# RelayBoard.net
KiCad netlist of a schematic drawn in Altium Designer
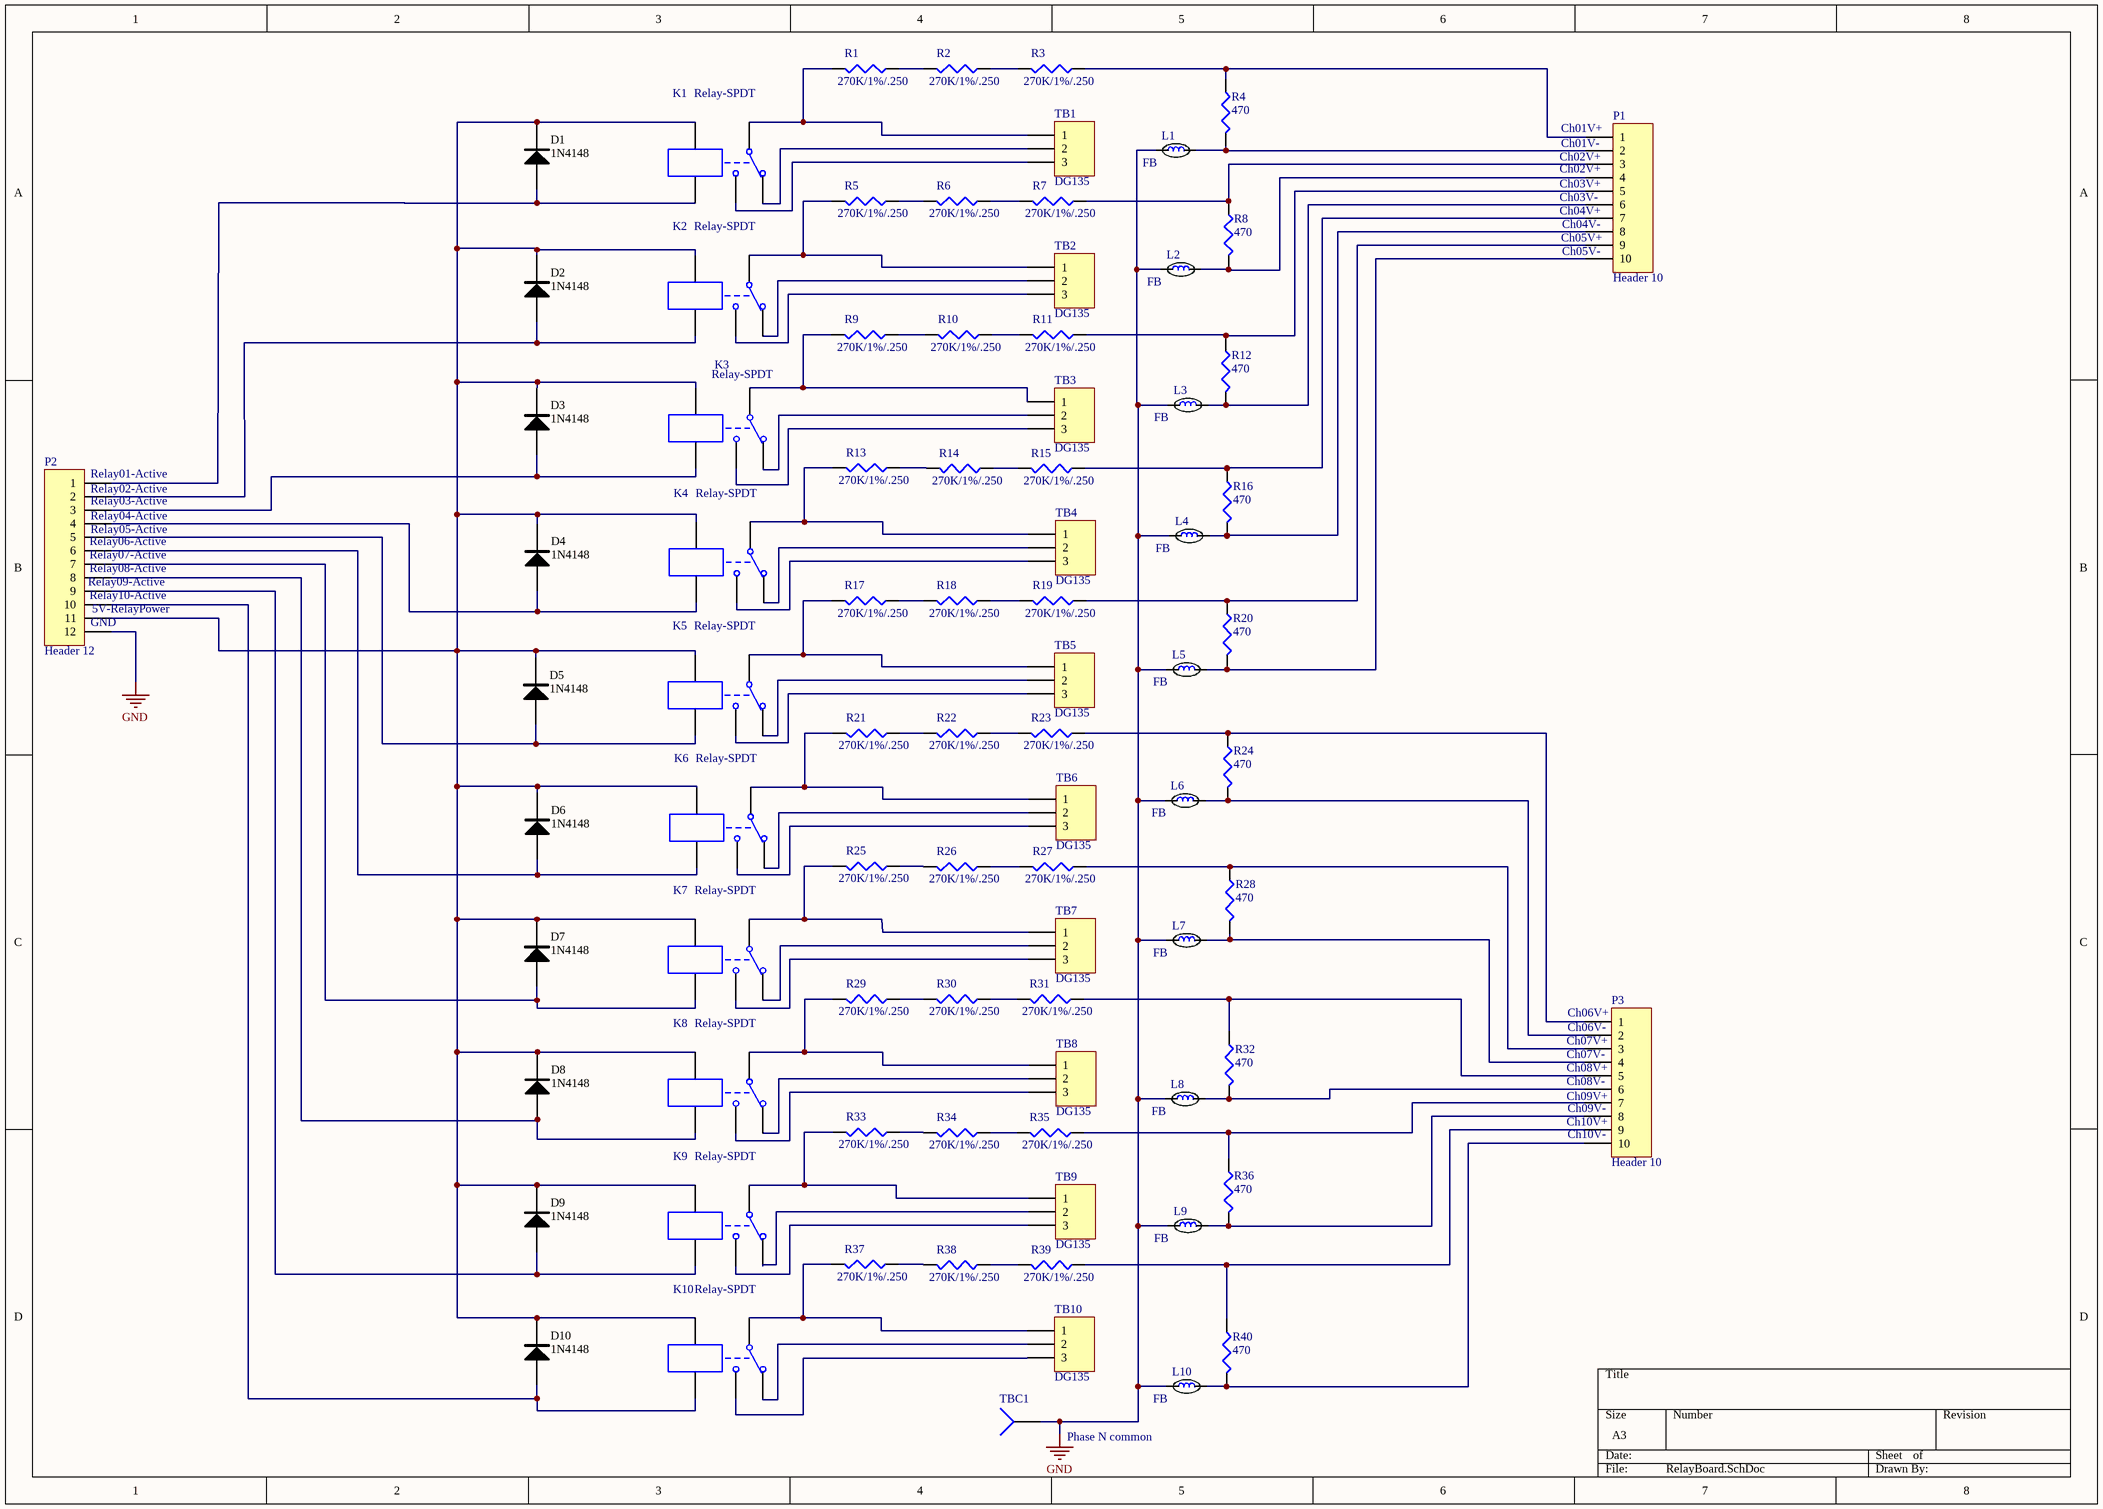
[diagram p0: RelayBoard.SchDoc]

(export (version "E")
  (design (tool "Eeschema 10.0.6"))
  (components
    (comp (ref "D1")
      (value "1N4148")
      (footprint "SOD523")
      (description "1N4001")
      (libsource (lib "vh_altium_library") (part "1N4001"))
    )
    (comp (ref "D2")
      (value "1N4148")
      (footprint "SOD523")
      (description "1N4001")
      (libsource (lib "vh_altium_library") (part "1N4001"))
    )
    (comp (ref "D3")
      (value "1N4148")
      (footprint "SOD523")
      (description "1N4001")
      (libsource (lib "vh_altium_library") (part "1N4001"))
    )
    (comp (ref "D4")
      (value "1N4148")
      (footprint "SOD523")
      (description "1N4001")
      (libsource (lib "vh_altium_library") (part "1N4001"))
    )
    (comp (ref "D5")
      (value "1N4148")
      (footprint "SOD523")
      (description "1N4001")
      (libsource (lib "vh_altium_library") (part "1N4001"))
    )
    (comp (ref "D6")
      (value "1N4148")
      (footprint "SOD523")
      (description "1N4001")
      (libsource (lib "vh_altium_library") (part "1N4001"))
    )
    (comp (ref "D7")
      (value "1N4148")
      (footprint "SOD523")
      (description "1N4001")
      (libsource (lib "vh_altium_library") (part "1N4001"))
    )
    (comp (ref "D8")
      (value "1N4148")
      (footprint "SOD523")
      (description "1N4001")
      (libsource (lib "vh_altium_library") (part "1N4001"))
    )
    (comp (ref "D9")
      (value "1N4148")
      (footprint "SOD523")
      (description "1N4001")
      (libsource (lib "vh_altium_library") (part "1N4001"))
    )
    (comp (ref "D10")
      (value "1N4148")
      (footprint "SOD523")
      (description "1N4001")
      (libsource (lib "vh_altium_library") (part "1N4001"))
    )
    (comp (ref "K1")
      (value "Relay-SPDT")
      (footprint "MODULE5B")
      (description "Single-Pole Dual-Throw Relay")
      (fields (field (name "PUBLISHER") "Altium Limited"))
      (libsource (lib "Miscellaneous Devices") (part "Relay-SPDT"))
    )
    (comp (ref "K2")
      (value "Relay-SPDT")
      (footprint "MODULE5B")
      (description "Single-Pole Dual-Throw Relay")
      (fields (field (name "PUBLISHER") "Altium Limited"))
      (libsource (lib "Miscellaneous Devices") (part "Relay-SPDT"))
    )
    (comp (ref "K3")
      (value "Relay-SPDT")
      (footprint "MODULE5B")
      (description "Single-Pole Dual-Throw Relay")
      (fields (field (name "PUBLISHER") "Altium Limited"))
      (libsource (lib "Miscellaneous Devices") (part "Relay-SPDT"))
    )
    (comp (ref "K4")
      (value "Relay-SPDT")
      (footprint "MODULE5B")
      (description "Single-Pole Dual-Throw Relay")
      (fields (field (name "PUBLISHER") "Altium Limited"))
      (libsource (lib "Miscellaneous Devices") (part "Relay-SPDT"))
    )
    (comp (ref "K5")
      (value "Relay-SPDT")
      (footprint "MODULE5B")
      (description "Single-Pole Dual-Throw Relay")
      (fields (field (name "PUBLISHER") "Altium Limited"))
      (libsource (lib "Miscellaneous Devices") (part "Relay-SPDT"))
    )
    (comp (ref "K6")
      (value "Relay-SPDT")
      (footprint "MODULE5B")
      (description "Single-Pole Dual-Throw Relay")
      (fields (field (name "PUBLISHER") "Altium Limited"))
      (libsource (lib "Miscellaneous Devices") (part "Relay-SPDT"))
    )
    (comp (ref "K7")
      (value "Relay-SPDT")
      (footprint "MODULE5B")
      (description "Single-Pole Dual-Throw Relay")
      (fields (field (name "PUBLISHER") "Altium Limited"))
      (libsource (lib "Miscellaneous Devices") (part "Relay-SPDT"))
    )
    (comp (ref "K8")
      (value "Relay-SPDT")
      (footprint "MODULE5B")
      (description "Single-Pole Dual-Throw Relay")
      (fields (field (name "PUBLISHER") "Altium Limited"))
      (libsource (lib "Miscellaneous Devices") (part "Relay-SPDT"))
    )
    (comp (ref "K9")
      (value "Relay-SPDT")
      (footprint "MODULE5B")
      (description "Single-Pole Dual-Throw Relay")
      (fields (field (name "PUBLISHER") "Altium Limited"))
      (libsource (lib "Miscellaneous Devices") (part "Relay-SPDT"))
    )
    (comp (ref "K10")
      (value "Relay-SPDT")
      (footprint "MODULE5B")
      (description "Single-Pole Dual-Throw Relay")
      (fields (field (name "PUBLISHER") "Altium Limited"))
      (libsource (lib "Miscellaneous Devices") (part "Relay-SPDT"))
    )
    (comp (ref "L1") (value "FB") (footprint "0603C-TBD") (libsource (lib "SMLib") (part "FerrBeads/ILBB")))
    (comp (ref "L2") (value "FB") (footprint "0603C-TBD") (libsource (lib "SMLib") (part "FerrBeads/ILBB")))
    (comp (ref "L3") (value "FB") (footprint "0603C-TBD") (libsource (lib "SMLib") (part "FerrBeads/ILBB")))
    (comp (ref "L4") (value "FB") (footprint "0603C-TBD") (libsource (lib "SMLib") (part "FerrBeads/ILBB")))
    (comp (ref "L5") (value "FB") (footprint "0603C-TBD") (libsource (lib "SMLib") (part "FerrBeads/ILBB")))
    (comp (ref "L6") (value "FB") (footprint "0603C-TBD") (libsource (lib "SMLib") (part "FerrBeads/ILBB")))
    (comp (ref "L7") (value "FB") (footprint "0603C-TBD") (libsource (lib "SMLib") (part "FerrBeads/ILBB")))
    (comp (ref "L8") (value "FB") (footprint "0603C-TBD") (libsource (lib "SMLib") (part "FerrBeads/ILBB")))
    (comp (ref "L9") (value "FB") (footprint "0603C-TBD") (libsource (lib "SMLib") (part "FerrBeads/ILBB")))
    (comp (ref "L10") (value "FB") (footprint "0603C-TBD") (libsource (lib "SMLib") (part "FerrBeads/ILBB")))
    (comp (ref "P1")
      (value "Header 10")
      (footprint "HDR1X10")
      (description "Header, 10-Pin")
      (fields (field (name "PUBLISHER") "Altium Limited"))
      (libsource (lib "Miscellaneous Connectors") (part "Header 10"))
    )
    (comp (ref "P2")
      (value "Header 12")
      (footprint "HDR1X12")
      (description "Header, 12-Pin")
      (fields (field (name "PUBLISHER") "Altium Limited"))
      (libsource (lib "Miscellaneous Connectors") (part "Header 12"))
    )
    (comp (ref "P3")
      (value "Header 10")
      (footprint "HDR1X10")
      (description "Header, 10-Pin")
      (fields (field (name "PUBLISHER") "Altium Limited"))
      (libsource (lib "Miscellaneous Connectors") (part "Header 10"))
    )
    (comp (ref "R1")
      (value "270K/1%/.250")
      (footprint "1210C-GENERIC")
      (description "Resistor")
      (fields (field (name "PUBLISHER") "Altium Limited"))
      (libsource (lib "Miscellaneous Devices") (part "Res3"))
    )
    (comp (ref "R2")
      (value "270K/1%/.250")
      (footprint "1210C-GENERIC")
      (description "Resistor")
      (fields (field (name "PUBLISHER") "Altium Limited"))
      (libsource (lib "Miscellaneous Devices") (part "Res3"))
    )
    (comp (ref "R3")
      (value "270K/1%/.250")
      (footprint "1210C-GENERIC")
      (description "Resistor")
      (fields (field (name "PUBLISHER") "Altium Limited"))
      (libsource (lib "Miscellaneous Devices") (part "Res3"))
    )
    (comp (ref "R4")
      (value "470")
      (footprint "1206C-GENERIC")
      (description "Resistor")
      (fields (field (name "PUBLISHER") "Altium Limited"))
      (libsource (lib "Miscellaneous Devices") (part "Res3"))
    )
    (comp (ref "R5")
      (value "270K/1%/.250")
      (footprint "1210C-GENERIC")
      (description "Resistor")
      (fields (field (name "PUBLISHER") "Altium Limited"))
      (libsource (lib "Miscellaneous Devices") (part "Res3"))
    )
    (comp (ref "R6")
      (value "270K/1%/.250")
      (footprint "1210C-GENERIC")
      (description "Resistor")
      (fields (field (name "PUBLISHER") "Altium Limited"))
      (libsource (lib "Miscellaneous Devices") (part "Res3"))
    )
    (comp (ref "R7")
      (value "270K/1%/.250")
      (footprint "1210C-GENERIC")
      (description "Resistor")
      (fields (field (name "PUBLISHER") "Altium Limited"))
      (libsource (lib "Miscellaneous Devices") (part "Res3"))
    )
    (comp (ref "R8")
      (value "470")
      (footprint "1206C-GENERIC")
      (description "Resistor")
      (fields (field (name "PUBLISHER") "Altium Limited"))
      (libsource (lib "Miscellaneous Devices") (part "Res3"))
    )
    (comp (ref "R9")
      (value "270K/1%/.250")
      (footprint "1210C-GENERIC")
      (description "Resistor")
      (fields (field (name "PUBLISHER") "Altium Limited"))
      (libsource (lib "Miscellaneous Devices") (part "Res3"))
    )
    (comp (ref "R10")
      (value "270K/1%/.250")
      (footprint "1210C-GENERIC")
      (description "Resistor")
      (fields (field (name "PUBLISHER") "Altium Limited"))
      (libsource (lib "Miscellaneous Devices") (part "Res3"))
    )
    (comp (ref "R11")
      (value "270K/1%/.250")
      (footprint "1210C-GENERIC")
      (description "Resistor")
      (fields (field (name "PUBLISHER") "Altium Limited"))
      (libsource (lib "Miscellaneous Devices") (part "Res3"))
    )
    (comp (ref "R12")
      (value "470")
      (footprint "1206C-GENERIC")
      (description "Resistor")
      (fields (field (name "PUBLISHER") "Altium Limited"))
      (libsource (lib "Miscellaneous Devices") (part "Res3"))
    )
    (comp (ref "R13")
      (value "270K/1%/.250")
      (footprint "1210C-GENERIC")
      (description "Resistor")
      (fields (field (name "PUBLISHER") "Altium Limited"))
      (libsource (lib "Miscellaneous Devices") (part "Res3"))
    )
    (comp (ref "R14")
      (value "270K/1%/.250")
      (footprint "1210C-GENERIC")
      (description "Resistor")
      (fields (field (name "PUBLISHER") "Altium Limited"))
      (libsource (lib "Miscellaneous Devices") (part "Res3"))
    )
    (comp (ref "R15")
      (value "270K/1%/.250")
      (footprint "1210C-GENERIC")
      (description "Resistor")
      (fields (field (name "PUBLISHER") "Altium Limited"))
      (libsource (lib "Miscellaneous Devices") (part "Res3"))
    )
    (comp (ref "R16")
      (value "470")
      (footprint "1206C-GENERIC")
      (description "Resistor")
      (fields (field (name "PUBLISHER") "Altium Limited"))
      (libsource (lib "Miscellaneous Devices") (part "Res3"))
    )
    (comp (ref "R17")
      (value "270K/1%/.250")
      (footprint "1210C-GENERIC")
      (description "Resistor")
      (fields (field (name "PUBLISHER") "Altium Limited"))
      (libsource (lib "Miscellaneous Devices") (part "Res3"))
    )
    (comp (ref "R18")
      (value "270K/1%/.250")
      (footprint "1210C-GENERIC")
      (description "Resistor")
      (fields (field (name "PUBLISHER") "Altium Limited"))
      (libsource (lib "Miscellaneous Devices") (part "Res3"))
    )
    (comp (ref "R19")
      (value "270K/1%/.250")
      (footprint "1210C-GENERIC")
      (description "Resistor")
      (fields (field (name "PUBLISHER") "Altium Limited"))
      (libsource (lib "Miscellaneous Devices") (part "Res3"))
    )
    (comp (ref "R20")
      (value "470")
      (footprint "1206C-GENERIC")
      (description "Resistor")
      (fields (field (name "PUBLISHER") "Altium Limited"))
      (libsource (lib "Miscellaneous Devices") (part "Res3"))
    )
    (comp (ref "R21")
      (value "270K/1%/.250")
      (footprint "1210C-GENERIC")
      (description "Resistor")
      (fields (field (name "PUBLISHER") "Altium Limited"))
      (libsource (lib "Miscellaneous Devices") (part "Res3"))
    )
    (comp (ref "R22")
      (value "270K/1%/.250")
      (footprint "1210C-GENERIC")
      (description "Resistor")
      (fields (field (name "PUBLISHER") "Altium Limited"))
      (libsource (lib "Miscellaneous Devices") (part "Res3"))
    )
    (comp (ref "R23")
      (value "270K/1%/.250")
      (footprint "1210C-GENERIC")
      (description "Resistor")
      (fields (field (name "PUBLISHER") "Altium Limited"))
      (libsource (lib "Miscellaneous Devices") (part "Res3"))
    )
    (comp (ref "R24")
      (value "470")
      (footprint "1206C-GENERIC")
      (description "Resistor")
      (fields (field (name "PUBLISHER") "Altium Limited"))
      (libsource (lib "Miscellaneous Devices") (part "Res3"))
    )
    (comp (ref "R25")
      (value "270K/1%/.250")
      (footprint "1210C-GENERIC")
      (description "Resistor")
      (fields (field (name "PUBLISHER") "Altium Limited"))
      (libsource (lib "Miscellaneous Devices") (part "Res3"))
    )
    (comp (ref "R26")
      (value "270K/1%/.250")
      (footprint "1210C-GENERIC")
      (description "Resistor")
      (fields (field (name "PUBLISHER") "Altium Limited"))
      (libsource (lib "Miscellaneous Devices") (part "Res3"))
    )
    (comp (ref "R27")
      (value "270K/1%/.250")
      (footprint "1210C-GENERIC")
      (description "Resistor")
      (fields (field (name "PUBLISHER") "Altium Limited"))
      (libsource (lib "Miscellaneous Devices") (part "Res3"))
    )
    (comp (ref "R28")
      (value "470")
      (footprint "1206C-GENERIC")
      (description "Resistor")
      (fields (field (name "PUBLISHER") "Altium Limited"))
      (libsource (lib "Miscellaneous Devices") (part "Res3"))
    )
    (comp (ref "R29")
      (value "270K/1%/.250")
      (footprint "1210C-GENERIC")
      (description "Resistor")
      (fields (field (name "PUBLISHER") "Altium Limited"))
      (libsource (lib "Miscellaneous Devices") (part "Res3"))
    )
    (comp (ref "R30")
      (value "270K/1%/.250")
      (footprint "1210C-GENERIC")
      (description "Resistor")
      (fields (field (name "PUBLISHER") "Altium Limited"))
      (libsource (lib "Miscellaneous Devices") (part "Res3"))
    )
    (comp (ref "R31")
      (value "270K/1%/.250")
      (footprint "1210C-GENERIC")
      (description "Resistor")
      (fields (field (name "PUBLISHER") "Altium Limited"))
      (libsource (lib "Miscellaneous Devices") (part "Res3"))
    )
    (comp (ref "R32")
      (value "470")
      (footprint "1206C-GENERIC")
      (description "Resistor")
      (fields (field (name "PUBLISHER") "Altium Limited"))
      (libsource (lib "Miscellaneous Devices") (part "Res3"))
    )
    (comp (ref "R33")
      (value "270K/1%/.250")
      (footprint "1210C-GENERIC")
      (description "Resistor")
      (fields (field (name "PUBLISHER") "Altium Limited"))
      (libsource (lib "Miscellaneous Devices") (part "Res3"))
    )
    (comp (ref "R34")
      (value "270K/1%/.250")
      (footprint "1210C-GENERIC")
      (description "Resistor")
      (fields (field (name "PUBLISHER") "Altium Limited"))
      (libsource (lib "Miscellaneous Devices") (part "Res3"))
    )
    (comp (ref "R35")
      (value "270K/1%/.250")
      (footprint "1210C-GENERIC")
      (description "Resistor")
      (fields (field (name "PUBLISHER") "Altium Limited"))
      (libsource (lib "Miscellaneous Devices") (part "Res3"))
    )
    (comp (ref "R36")
      (value "470")
      (footprint "1206C-GENERIC")
      (description "Resistor")
      (fields (field (name "PUBLISHER") "Altium Limited"))
      (libsource (lib "Miscellaneous Devices") (part "Res3"))
    )
    (comp (ref "R37")
      (value "270K/1%/.250")
      (footprint "1210C-GENERIC")
      (description "Resistor")
      (fields (field (name "PUBLISHER") "Altium Limited"))
      (libsource (lib "Miscellaneous Devices") (part "Res3"))
    )
    (comp (ref "R38")
      (value "270K/1%/.250")
      (footprint "1210C-GENERIC")
      (description "Resistor")
      (fields (field (name "PUBLISHER") "Altium Limited"))
      (libsource (lib "Miscellaneous Devices") (part "Res3"))
    )
    (comp (ref "R39")
      (value "270K/1%/.250")
      (footprint "1210C-GENERIC")
      (description "Resistor")
      (fields (field (name "PUBLISHER") "Altium Limited"))
      (libsource (lib "Miscellaneous Devices") (part "Res3"))
    )
    (comp (ref "R40")
      (value "470")
      (footprint "1206C-GENERIC")
      (description "Resistor")
      (fields (field (name "PUBLISHER") "Altium Limited"))
      (libsource (lib "Miscellaneous Devices") (part "Res3"))
    )
    (comp (ref "TB1")
      (value "DG135")
      (footprint "DG135-1")
      (description "Header, 3-Pin")
      (fields (field (name "PUBLISHER") "Altium Limited"))
      (libsource (lib "Miscellaneous Connectors") (part "Header 3"))
    )
    (comp (ref "TB2")
      (value "DG135")
      (footprint "DG135-1")
      (description "Header, 3-Pin")
      (fields (field (name "PUBLISHER") "Altium Limited"))
      (libsource (lib "Miscellaneous Connectors") (part "Header 3"))
    )
    (comp (ref "TB3")
      (value "DG135")
      (footprint "DG135-1")
      (description "Header, 3-Pin")
      (fields (field (name "PUBLISHER") "Altium Limited"))
      (libsource (lib "Miscellaneous Connectors") (part "Header 3"))
    )
    (comp (ref "TB4")
      (value "DG135")
      (footprint "DG135-1")
      (description "Header, 3-Pin")
      (fields (field (name "PUBLISHER") "Altium Limited"))
      (libsource (lib "Miscellaneous Connectors") (part "Header 3"))
    )
    (comp (ref "TB5")
      (value "DG135")
      (footprint "DG135-1")
      (description "Header, 3-Pin")
      (fields (field (name "PUBLISHER") "Altium Limited"))
      (libsource (lib "Miscellaneous Connectors") (part "Header 3"))
    )
    (comp (ref "TB6")
      (value "DG135")
      (footprint "DG135-1")
      (description "Header, 3-Pin")
      (fields (field (name "PUBLISHER") "Altium Limited"))
      (libsource (lib "Miscellaneous Connectors") (part "Header 3"))
    )
    (comp (ref "TB7")
      (value "DG135")
      (footprint "DG135-1")
      (description "Header, 3-Pin")
      (fields (field (name "PUBLISHER") "Altium Limited"))
      (libsource (lib "Miscellaneous Connectors") (part "Header 3"))
    )
    (comp (ref "TB8")
      (value "DG135")
      (footprint "DG135-1")
      (description "Header, 3-Pin")
      (fields (field (name "PUBLISHER") "Altium Limited"))
      (libsource (lib "Miscellaneous Connectors") (part "Header 3"))
    )
    (comp (ref "TB9")
      (value "DG135")
      (footprint "DG135-1")
      (description "Header, 3-Pin")
      (fields (field (name "PUBLISHER") "Altium Limited"))
      (libsource (lib "Miscellaneous Connectors") (part "Header 3"))
    )
    (comp (ref "TB10")
      (value "DG135")
      (footprint "DG135-1")
      (description "Header, 3-Pin")
      (fields (field (name "PUBLISHER") "Altium Limited"))
      (libsource (lib "Miscellaneous Connectors") (part "Header 3"))
    )
    (comp (ref "TBC1")
      (value "TBcommon")
      (footprint "PIN1")
      (description "Socket")
      (fields (field (name "PUBLISHER") "Altium Limited"))
      (libsource (lib "Miscellaneous Connectors") (part "Socket"))
    )
  )
  (nets
    (net (code "1") (name "GND") (class "Default")
      (node (ref "L1") (pin "1") (pinfunction "1_1") (pintype "passive"))
      (node (ref "L10") (pin "1") (pinfunction "1_1") (pintype "passive"))
      (node (ref "L2") (pin "1") (pinfunction "1_1") (pintype "passive"))
      (node (ref "L3") (pin "1") (pinfunction "1_1") (pintype "passive"))
      (node (ref "L4") (pin "1") (pinfunction "1_1") (pintype "passive"))
      (node (ref "L5") (pin "1") (pinfunction "1_1") (pintype "passive"))
      (node (ref "L6") (pin "1") (pinfunction "1_1") (pintype "passive"))
      (node (ref "L7") (pin "1") (pinfunction "1_1") (pintype "passive"))
      (node (ref "L8") (pin "1") (pinfunction "1_1") (pintype "passive"))
      (node (ref "L9") (pin "1") (pinfunction "1_1") (pintype "passive"))
      (node (ref "P2") (pin "12") (pinfunction "12_12") (pintype "passive"))
      (node (ref "TBC1") (pin "1") (pinfunction "1_1") (pintype "passive"))
    )
    (net (code "2") (name "Net-(D1-PadA)") (class "Default")
      (node (ref "D1") (pin "A") (pinfunction "A_A") (pintype "passive"))
      (node (ref "K1") (pin "2") (pinfunction "2_2") (pintype "passive"))
      (node (ref "P2") (pin "1") (pinfunction "1_1") (pintype "passive"))
    )
    (net (code "3") (name "Net-(D1-PadK)") (class "Default")
      (node (ref "D1") (pin "K") (pinfunction "K_K") (pintype "passive"))
      (node (ref "D10") (pin "K") (pinfunction "K_K") (pintype "passive"))
      (node (ref "D2") (pin "K") (pinfunction "K_K") (pintype "passive"))
      (node (ref "D3") (pin "K") (pinfunction "K_K") (pintype "passive"))
      (node (ref "D4") (pin "K") (pinfunction "K_K") (pintype "passive"))
      (node (ref "D5") (pin "K") (pinfunction "K_K") (pintype "passive"))
      (node (ref "D6") (pin "K") (pinfunction "K_K") (pintype "passive"))
      (node (ref "D7") (pin "K") (pinfunction "K_K") (pintype "passive"))
      (node (ref "D8") (pin "K") (pinfunction "K_K") (pintype "passive"))
      (node (ref "D9") (pin "K") (pinfunction "K_K") (pintype "passive"))
      (node (ref "K1") (pin "1") (pinfunction "1_1") (pintype "passive"))
      (node (ref "K10") (pin "1") (pinfunction "1_1") (pintype "passive"))
      (node (ref "K2") (pin "1") (pinfunction "1_1") (pintype "passive"))
      (node (ref "K3") (pin "1") (pinfunction "1_1") (pintype "passive"))
      (node (ref "K4") (pin "1") (pinfunction "1_1") (pintype "passive"))
      (node (ref "K5") (pin "1") (pinfunction "1_1") (pintype "passive"))
      (node (ref "K6") (pin "1") (pinfunction "1_1") (pintype "passive"))
      (node (ref "K7") (pin "1") (pinfunction "1_1") (pintype "passive"))
      (node (ref "K8") (pin "1") (pinfunction "1_1") (pintype "passive"))
      (node (ref "K9") (pin "1") (pinfunction "1_1") (pintype "passive"))
      (node (ref "P2") (pin "11") (pinfunction "11_11") (pintype "passive"))
    )
    (net (code "4") (name "Net-(D2-PadA)") (class "Default")
      (node (ref "D2") (pin "A") (pinfunction "A_A") (pintype "passive"))
      (node (ref "K2") (pin "2") (pinfunction "2_2") (pintype "passive"))
      (node (ref "P2") (pin "2") (pinfunction "2_2") (pintype "passive"))
    )
    (net (code "5") (name "Net-(D3-PadA)") (class "Default")
      (node (ref "D3") (pin "A") (pinfunction "A_A") (pintype "passive"))
      (node (ref "K3") (pin "2") (pinfunction "2_2") (pintype "passive"))
      (node (ref "P2") (pin "3") (pinfunction "3_3") (pintype "passive"))
    )
    (net (code "6") (name "Net-(D4-PadA)") (class "Default")
      (node (ref "D4") (pin "A") (pinfunction "A_A") (pintype "passive"))
      (node (ref "K4") (pin "2") (pinfunction "2_2") (pintype "passive"))
      (node (ref "P2") (pin "4") (pinfunction "4_4") (pintype "passive"))
    )
    (net (code "7") (name "Net-(D5-PadA)") (class "Default")
      (node (ref "D5") (pin "A") (pinfunction "A_A") (pintype "passive"))
      (node (ref "K5") (pin "2") (pinfunction "2_2") (pintype "passive"))
      (node (ref "P2") (pin "5") (pinfunction "5_5") (pintype "passive"))
    )
    (net (code "8") (name "Net-(D6-PadA)") (class "Default")
      (node (ref "D6") (pin "A") (pinfunction "A_A") (pintype "passive"))
      (node (ref "K6") (pin "2") (pinfunction "2_2") (pintype "passive"))
      (node (ref "P2") (pin "6") (pinfunction "6_6") (pintype "passive"))
    )
    (net (code "9") (name "Net-(D7-PadA)") (class "Default")
      (node (ref "D7") (pin "A") (pinfunction "A_A") (pintype "passive"))
      (node (ref "K7") (pin "2") (pinfunction "2_2") (pintype "passive"))
      (node (ref "P2") (pin "7") (pinfunction "7_7") (pintype "passive"))
    )
    (net (code "10") (name "Net-(D8-PadA)") (class "Default")
      (node (ref "D8") (pin "A") (pinfunction "A_A") (pintype "passive"))
      (node (ref "K8") (pin "2") (pinfunction "2_2") (pintype "passive"))
      (node (ref "P2") (pin "8") (pinfunction "8_8") (pintype "passive"))
    )
    (net (code "11") (name "Net-(D9-PadA)") (class "Default")
      (node (ref "D9") (pin "A") (pinfunction "A_A") (pintype "passive"))
      (node (ref "K9") (pin "2") (pinfunction "2_2") (pintype "passive"))
      (node (ref "P2") (pin "9") (pinfunction "9_9") (pintype "passive"))
    )
    (net (code "12") (name "Net-(D10-PadA)") (class "Default")
      (node (ref "D10") (pin "A") (pinfunction "A_A") (pintype "passive"))
      (node (ref "K10") (pin "2") (pinfunction "2_2") (pintype "passive"))
      (node (ref "P2") (pin "10") (pinfunction "10_10") (pintype "passive"))
    )
    (net (code "13") (name "Net-(K1-Pad3)") (class "Default")
      (node (ref "K1") (pin "3") (pinfunction "3_3") (pintype "passive"))
      (node (ref "TB1") (pin "3") (pinfunction "3_3") (pintype "passive"))
    )
    (net (code "14") (name "Net-(K1-Pad4)") (class "Default")
      (node (ref "K1") (pin "4") (pinfunction "4_4") (pintype "passive"))
      (node (ref "R1") (pin "2") (pinfunction "2_2") (pintype "passive"))
      (node (ref "TB1") (pin "1") (pinfunction "1_1") (pintype "passive"))
    )
    (net (code "15") (name "Net-(K1-Pad5)") (class "Default")
      (node (ref "K1") (pin "5") (pinfunction "5_5") (pintype "passive"))
      (node (ref "TB1") (pin "2") (pinfunction "2_2") (pintype "passive"))
    )
    (net (code "16") (name "Net-(K2-Pad3)") (class "Default")
      (node (ref "K2") (pin "3") (pinfunction "3_3") (pintype "passive"))
      (node (ref "TB2") (pin "3") (pinfunction "3_3") (pintype "passive"))
    )
    (net (code "17") (name "Net-(K2-Pad4)") (class "Default")
      (node (ref "K2") (pin "4") (pinfunction "4_4") (pintype "passive"))
      (node (ref "R5") (pin "2") (pinfunction "2_2") (pintype "passive"))
      (node (ref "TB2") (pin "1") (pinfunction "1_1") (pintype "passive"))
    )
    (net (code "18") (name "Net-(K2-Pad5)") (class "Default")
      (node (ref "K2") (pin "5") (pinfunction "5_5") (pintype "passive"))
      (node (ref "TB2") (pin "2") (pinfunction "2_2") (pintype "passive"))
    )
    (net (code "19") (name "Net-(K3-Pad3)") (class "Default")
      (node (ref "K3") (pin "3") (pinfunction "3_3") (pintype "passive"))
      (node (ref "TB3") (pin "3") (pinfunction "3_3") (pintype "passive"))
    )
    (net (code "20") (name "Net-(K3-Pad4)") (class "Default")
      (node (ref "K3") (pin "4") (pinfunction "4_4") (pintype "passive"))
      (node (ref "R9") (pin "2") (pinfunction "2_2") (pintype "passive"))
      (node (ref "TB3") (pin "1") (pinfunction "1_1") (pintype "passive"))
    )
    (net (code "21") (name "Net-(K3-Pad5)") (class "Default")
      (node (ref "K3") (pin "5") (pinfunction "5_5") (pintype "passive"))
      (node (ref "TB3") (pin "2") (pinfunction "2_2") (pintype "passive"))
    )
    (net (code "22") (name "Net-(K4-Pad3)") (class "Default")
      (node (ref "K4") (pin "3") (pinfunction "3_3") (pintype "passive"))
      (node (ref "TB4") (pin "3") (pinfunction "3_3") (pintype "passive"))
    )
    (net (code "23") (name "Net-(K4-Pad4)") (class "Default")
      (node (ref "K4") (pin "4") (pinfunction "4_4") (pintype "passive"))
      (node (ref "R13") (pin "2") (pinfunction "2_2") (pintype "passive"))
      (node (ref "TB4") (pin "1") (pinfunction "1_1") (pintype "passive"))
    )
    (net (code "24") (name "Net-(K4-Pad5)") (class "Default")
      (node (ref "K4") (pin "5") (pinfunction "5_5") (pintype "passive"))
      (node (ref "TB4") (pin "2") (pinfunction "2_2") (pintype "passive"))
    )
    (net (code "25") (name "Net-(K5-Pad3)") (class "Default")
      (node (ref "K5") (pin "3") (pinfunction "3_3") (pintype "passive"))
      (node (ref "TB5") (pin "3") (pinfunction "3_3") (pintype "passive"))
    )
    (net (code "26") (name "Net-(K5-Pad4)") (class "Default")
      (node (ref "K5") (pin "4") (pinfunction "4_4") (pintype "passive"))
      (node (ref "R17") (pin "2") (pinfunction "2_2") (pintype "passive"))
      (node (ref "TB5") (pin "1") (pinfunction "1_1") (pintype "passive"))
    )
    (net (code "27") (name "Net-(K5-Pad5)") (class "Default")
      (node (ref "K5") (pin "5") (pinfunction "5_5") (pintype "passive"))
      (node (ref "TB5") (pin "2") (pinfunction "2_2") (pintype "passive"))
    )
    (net (code "28") (name "Net-(K6-Pad3)") (class "Default")
      (node (ref "K6") (pin "3") (pinfunction "3_3") (pintype "passive"))
      (node (ref "TB6") (pin "3") (pinfunction "3_3") (pintype "passive"))
    )
    (net (code "29") (name "Net-(K6-Pad4)") (class "Default")
      (node (ref "K6") (pin "4") (pinfunction "4_4") (pintype "passive"))
      (node (ref "R21") (pin "2") (pinfunction "2_2") (pintype "passive"))
      (node (ref "TB6") (pin "1") (pinfunction "1_1") (pintype "passive"))
    )
    (net (code "30") (name "Net-(K6-Pad5)") (class "Default")
      (node (ref "K6") (pin "5") (pinfunction "5_5") (pintype "passive"))
      (node (ref "TB6") (pin "2") (pinfunction "2_2") (pintype "passive"))
    )
    (net (code "31") (name "Net-(K7-Pad3)") (class "Default")
      (node (ref "K7") (pin "3") (pinfunction "3_3") (pintype "passive"))
      (node (ref "TB7") (pin "3") (pinfunction "3_3") (pintype "passive"))
    )
    (net (code "32") (name "Net-(K7-Pad4)") (class "Default")
      (node (ref "K7") (pin "4") (pinfunction "4_4") (pintype "passive"))
      (node (ref "R25") (pin "2") (pinfunction "2_2") (pintype "passive"))
      (node (ref "TB7") (pin "1") (pinfunction "1_1") (pintype "passive"))
    )
    (net (code "33") (name "Net-(K7-Pad5)") (class "Default")
      (node (ref "K7") (pin "5") (pinfunction "5_5") (pintype "passive"))
      (node (ref "TB7") (pin "2") (pinfunction "2_2") (pintype "passive"))
    )
    (net (code "34") (name "Net-(K8-Pad3)") (class "Default")
      (node (ref "K8") (pin "3") (pinfunction "3_3") (pintype "passive"))
      (node (ref "TB8") (pin "3") (pinfunction "3_3") (pintype "passive"))
    )
    (net (code "35") (name "Net-(K8-Pad4)") (class "Default")
      (node (ref "K8") (pin "4") (pinfunction "4_4") (pintype "passive"))
      (node (ref "R29") (pin "2") (pinfunction "2_2") (pintype "passive"))
      (node (ref "TB8") (pin "1") (pinfunction "1_1") (pintype "passive"))
    )
    (net (code "36") (name "Net-(K8-Pad5)") (class "Default")
      (node (ref "K8") (pin "5") (pinfunction "5_5") (pintype "passive"))
      (node (ref "TB8") (pin "2") (pinfunction "2_2") (pintype "passive"))
    )
    (net (code "37") (name "Net-(K9-Pad3)") (class "Default")
      (node (ref "K9") (pin "3") (pinfunction "3_3") (pintype "passive"))
      (node (ref "TB9") (pin "3") (pinfunction "3_3") (pintype "passive"))
    )
    (net (code "38") (name "Net-(K9-Pad4)") (class "Default")
      (node (ref "K9") (pin "4") (pinfunction "4_4") (pintype "passive"))
      (node (ref "R33") (pin "2") (pinfunction "2_2") (pintype "passive"))
      (node (ref "TB9") (pin "1") (pinfunction "1_1") (pintype "passive"))
    )
    (net (code "39") (name "Net-(K9-Pad5)") (class "Default")
      (node (ref "K9") (pin "5") (pinfunction "5_5") (pintype "passive"))
      (node (ref "TB9") (pin "2") (pinfunction "2_2") (pintype "passive"))
    )
    (net (code "40") (name "Net-(K10-Pad3)") (class "Default")
      (node (ref "K10") (pin "3") (pinfunction "3_3") (pintype "passive"))
      (node (ref "TB10") (pin "3") (pinfunction "3_3") (pintype "passive"))
    )
    (net (code "41") (name "Net-(K10-Pad4)") (class "Default")
      (node (ref "K10") (pin "4") (pinfunction "4_4") (pintype "passive"))
      (node (ref "R37") (pin "2") (pinfunction "2_2") (pintype "passive"))
      (node (ref "TB10") (pin "1") (pinfunction "1_1") (pintype "passive"))
    )
    (net (code "42") (name "Net-(K10-Pad5)") (class "Default")
      (node (ref "K10") (pin "5") (pinfunction "5_5") (pintype "passive"))
      (node (ref "TB10") (pin "2") (pinfunction "2_2") (pintype "passive"))
    )
    (net (code "43") (name "Net-(L1-Pad2)") (class "Default")
      (node (ref "L1") (pin "2") (pinfunction "2_2") (pintype "passive"))
      (node (ref "P1") (pin "2") (pinfunction "2_2") (pintype "passive"))
      (node (ref "R4") (pin "2") (pinfunction "2_2") (pintype "passive"))
    )
    (net (code "44") (name "Net-(L2-Pad2)") (class "Default")
      (node (ref "L2") (pin "2") (pinfunction "2_2") (pintype "passive"))
      (node (ref "P1") (pin "4") (pinfunction "4_4") (pintype "passive"))
    )
    (net (code "45") (name "Net-(L3-Pad2)") (class "Default")
      (node (ref "L3") (pin "2") (pinfunction "2_2") (pintype "passive"))
      (node (ref "P1") (pin "6") (pinfunction "6_6") (pintype "passive"))
      (node (ref "R12") (pin "2") (pinfunction "2_2") (pintype "passive"))
    )
    (net (code "46") (name "Net-(L4-Pad2)") (class "Default")
      (node (ref "L4") (pin "2") (pinfunction "2_2") (pintype "passive"))
      (node (ref "P1") (pin "8") (pinfunction "8_8") (pintype "passive"))
      (node (ref "R16") (pin "2") (pinfunction "2_2") (pintype "passive"))
    )
    (net (code "47") (name "Net-(L5-Pad2)") (class "Default")
      (node (ref "L5") (pin "2") (pinfunction "2_2") (pintype "passive"))
      (node (ref "P1") (pin "10") (pinfunction "10_10") (pintype "passive"))
    )
    (net (code "48") (name "Net-(L6-Pad2)") (class "Default")
      (node (ref "L6") (pin "2") (pinfunction "2_2") (pintype "passive"))
      (node (ref "P3") (pin "2") (pinfunction "2_2") (pintype "passive"))
      (node (ref "R24") (pin "2") (pinfunction "2_2") (pintype "passive"))
    )
    (net (code "49") (name "Net-(L7-Pad2)") (class "Default")
      (node (ref "L7") (pin "2") (pinfunction "2_2") (pintype "passive"))
      (node (ref "P3") (pin "4") (pinfunction "4_4") (pintype "passive"))
      (node (ref "R28") (pin "2") (pinfunction "2_2") (pintype "passive"))
    )
    (net (code "50") (name "Net-(L8-Pad2)") (class "Default")
      (node (ref "L8") (pin "2") (pinfunction "2_2") (pintype "passive"))
      (node (ref "P3") (pin "6") (pinfunction "6_6") (pintype "passive"))
      (node (ref "R32") (pin "2") (pinfunction "2_2") (pintype "passive"))
    )
    (net (code "51") (name "Net-(L9-Pad2)") (class "Default")
      (node (ref "L9") (pin "2") (pinfunction "2_2") (pintype "passive"))
      (node (ref "P3") (pin "8") (pinfunction "8_8") (pintype "passive"))
      (node (ref "R36") (pin "2") (pinfunction "2_2") (pintype "passive"))
    )
    (net (code "52") (name "Net-(L10-Pad2)") (class "Default")
      (node (ref "L10") (pin "2") (pinfunction "2_2") (pintype "passive"))
      (node (ref "P3") (pin "10") (pinfunction "10_10") (pintype "passive"))
      (node (ref "R40") (pin "2") (pinfunction "2_2") (pintype "passive"))
    )
    (net (code "53") (name "Net-(P1-Pad1)") (class "Default")
      (node (ref "P1") (pin "1") (pinfunction "1_1") (pintype "passive"))
      (node (ref "R3") (pin "1") (pinfunction "1_1") (pintype "passive"))
      (node (ref "R4") (pin "1") (pinfunction "1_1") (pintype "passive"))
    )
    (net (code "54") (name "Net-(P1-Pad3)") (class "Default")
      (node (ref "P1") (pin "3") (pinfunction "3_3") (pintype "passive"))
      (node (ref "R7") (pin "1") (pinfunction "1_1") (pintype "passive"))
      (node (ref "R8") (pin "1") (pinfunction "1_1") (pintype "passive"))
    )
    (net (code "55") (name "Net-(P1-Pad5)") (class "Default")
      (node (ref "P1") (pin "5") (pinfunction "5_5") (pintype "passive"))
      (node (ref "R11") (pin "1") (pinfunction "1_1") (pintype "passive"))
      (node (ref "R12") (pin "1") (pinfunction "1_1") (pintype "passive"))
    )
    (net (code "56") (name "Net-(P1-Pad7)") (class "Default")
      (node (ref "P1") (pin "7") (pinfunction "7_7") (pintype "passive"))
      (node (ref "R15") (pin "1") (pinfunction "1_1") (pintype "passive"))
      (node (ref "R16") (pin "1") (pinfunction "1_1") (pintype "passive"))
    )
    (net (code "57") (name "Net-(P1-Pad9)") (class "Default")
      (node (ref "P1") (pin "9") (pinfunction "9_9") (pintype "passive"))
      (node (ref "R19") (pin "1") (pinfunction "1_1") (pintype "passive"))
      (node (ref "R20") (pin "1") (pinfunction "1_1") (pintype "passive"))
    )
    (net (code "58") (name "Net-(P3-Pad1)") (class "Default")
      (node (ref "P3") (pin "1") (pinfunction "1_1") (pintype "passive"))
      (node (ref "R23") (pin "1") (pinfunction "1_1") (pintype "passive"))
      (node (ref "R24") (pin "1") (pinfunction "1_1") (pintype "passive"))
    )
    (net (code "59") (name "Net-(P3-Pad3)") (class "Default")
      (node (ref "P3") (pin "3") (pinfunction "3_3") (pintype "passive"))
      (node (ref "R27") (pin "1") (pinfunction "1_1") (pintype "passive"))
      (node (ref "R28") (pin "1") (pinfunction "1_1") (pintype "passive"))
    )
    (net (code "60") (name "Net-(P3-Pad5)") (class "Default")
      (node (ref "P3") (pin "5") (pinfunction "5_5") (pintype "passive"))
      (node (ref "R31") (pin "1") (pinfunction "1_1") (pintype "passive"))
      (node (ref "R32") (pin "1") (pinfunction "1_1") (pintype "passive"))
    )
    (net (code "61") (name "Net-(P3-Pad7)") (class "Default")
      (node (ref "P3") (pin "7") (pinfunction "7_7") (pintype "passive"))
      (node (ref "R35") (pin "1") (pinfunction "1_1") (pintype "passive"))
      (node (ref "R36") (pin "1") (pinfunction "1_1") (pintype "passive"))
    )
    (net (code "62") (name "Net-(P3-Pad9)") (class "Default")
      (node (ref "P3") (pin "9") (pinfunction "9_9") (pintype "passive"))
      (node (ref "R39") (pin "1") (pinfunction "1_1") (pintype "passive"))
      (node (ref "R40") (pin "1") (pinfunction "1_1") (pintype "passive"))
    )
    (net (code "63") (name "Net-(R1-Pad1)") (class "Default")
      (node (ref "R1") (pin "1") (pinfunction "1_1") (pintype "passive"))
      (node (ref "R2") (pin "2") (pinfunction "2_2") (pintype "passive"))
    )
    (net (code "64") (name "Net-(R2-Pad1)") (class "Default")
      (node (ref "R2") (pin "1") (pinfunction "1_1") (pintype "passive"))
      (node (ref "R3") (pin "2") (pinfunction "2_2") (pintype "passive"))
    )
    (net (code "65") (name "Net-(R5-Pad1)") (class "Default")
      (node (ref "R5") (pin "1") (pinfunction "1_1") (pintype "passive"))
      (node (ref "R6") (pin "2") (pinfunction "2_2") (pintype "passive"))
    )
    (net (code "66") (name "Net-(R6-Pad1)") (class "Default")
      (node (ref "R6") (pin "1") (pinfunction "1_1") (pintype "passive"))
      (node (ref "R7") (pin "2") (pinfunction "2_2") (pintype "passive"))
    )
    (net (code "67") (name "Net-(R10-Pad1)") (class "Default")
      (node (ref "R10") (pin "1") (pinfunction "1_1") (pintype "passive"))
      (node (ref "R11") (pin "2") (pinfunction "2_2") (pintype "passive"))
    )
    (net (code "68") (name "Net-(R10-Pad2)") (class "Default")
      (node (ref "R10") (pin "2") (pinfunction "2_2") (pintype "passive"))
      (node (ref "R9") (pin "1") (pinfunction "1_1") (pintype "passive"))
    )
    (net (code "69") (name "Net-(R13-Pad1)") (class "Default")
      (node (ref "R13") (pin "1") (pinfunction "1_1") (pintype "passive"))
      (node (ref "R14") (pin "2") (pinfunction "2_2") (pintype "passive"))
    )
    (net (code "70") (name "Net-(R14-Pad1)") (class "Default")
      (node (ref "R14") (pin "1") (pinfunction "1_1") (pintype "passive"))
      (node (ref "R15") (pin "2") (pinfunction "2_2") (pintype "passive"))
    )
    (net (code "71") (name "Net-(R17-Pad1)") (class "Default")
      (node (ref "R17") (pin "1") (pinfunction "1_1") (pintype "passive"))
      (node (ref "R18") (pin "2") (pinfunction "2_2") (pintype "passive"))
    )
    (net (code "72") (name "Net-(R18-Pad1)") (class "Default")
      (node (ref "R18") (pin "1") (pinfunction "1_1") (pintype "passive"))
      (node (ref "R19") (pin "2") (pinfunction "2_2") (pintype "passive"))
    )
    (net (code "73") (name "Net-(R21-Pad1)") (class "Default")
      (node (ref "R21") (pin "1") (pinfunction "1_1") (pintype "passive"))
      (node (ref "R22") (pin "2") (pinfunction "2_2") (pintype "passive"))
    )
    (net (code "74") (name "Net-(R22-Pad1)") (class "Default")
      (node (ref "R22") (pin "1") (pinfunction "1_1") (pintype "passive"))
      (node (ref "R23") (pin "2") (pinfunction "2_2") (pintype "passive"))
    )
    (net (code "75") (name "Net-(R25-Pad1)") (class "Default")
      (node (ref "R25") (pin "1") (pinfunction "1_1") (pintype "passive"))
      (node (ref "R26") (pin "2") (pinfunction "2_2") (pintype "passive"))
    )
    (net (code "76") (name "Net-(R26-Pad1)") (class "Default")
      (node (ref "R26") (pin "1") (pinfunction "1_1") (pintype "passive"))
      (node (ref "R27") (pin "2") (pinfunction "2_2") (pintype "passive"))
    )
    (net (code "77") (name "Net-(R29-Pad1)") (class "Default")
      (node (ref "R29") (pin "1") (pinfunction "1_1") (pintype "passive"))
      (node (ref "R30") (pin "2") (pinfunction "2_2") (pintype "passive"))
    )
    (net (code "78") (name "Net-(R30-Pad1)") (class "Default")
      (node (ref "R30") (pin "1") (pinfunction "1_1") (pintype "passive"))
      (node (ref "R31") (pin "2") (pinfunction "2_2") (pintype "passive"))
    )
    (net (code "79") (name "Net-(R33-Pad1)") (class "Default")
      (node (ref "R33") (pin "1") (pinfunction "1_1") (pintype "passive"))
      (node (ref "R34") (pin "2") (pinfunction "2_2") (pintype "passive"))
    )
    (net (code "80") (name "Net-(R34-Pad1)") (class "Default")
      (node (ref "R34") (pin "1") (pinfunction "1_1") (pintype "passive"))
      (node (ref "R35") (pin "2") (pinfunction "2_2") (pintype "passive"))
    )
    (net (code "81") (name "Net-(R37-Pad1)") (class "Default")
      (node (ref "R37") (pin "1") (pinfunction "1_1") (pintype "passive"))
      (node (ref "R38") (pin "2") (pinfunction "2_2") (pintype "passive"))
    )
    (net (code "82") (name "Net-(R38-Pad1)") (class "Default")
      (node (ref "R38") (pin "1") (pinfunction "1_1") (pintype "passive"))
      (node (ref "R39") (pin "2") (pinfunction "2_2") (pintype "passive"))
    )
    (net (code "83") (name "unconnected-(R8-Pad2)") (class "Default")
      (node (ref "R8") (pin "2") (pinfunction "2_2") (pintype "passive"))
    )
    (net (code "84") (name "unconnected-(R20-Pad2)") (class "Default")
      (node (ref "R20") (pin "2") (pinfunction "2_2") (pintype "passive"))
    )
  )
)
